# PD_Receiver_Circuit.net
KiCad netlist of a schematic drawn in Altium Designer
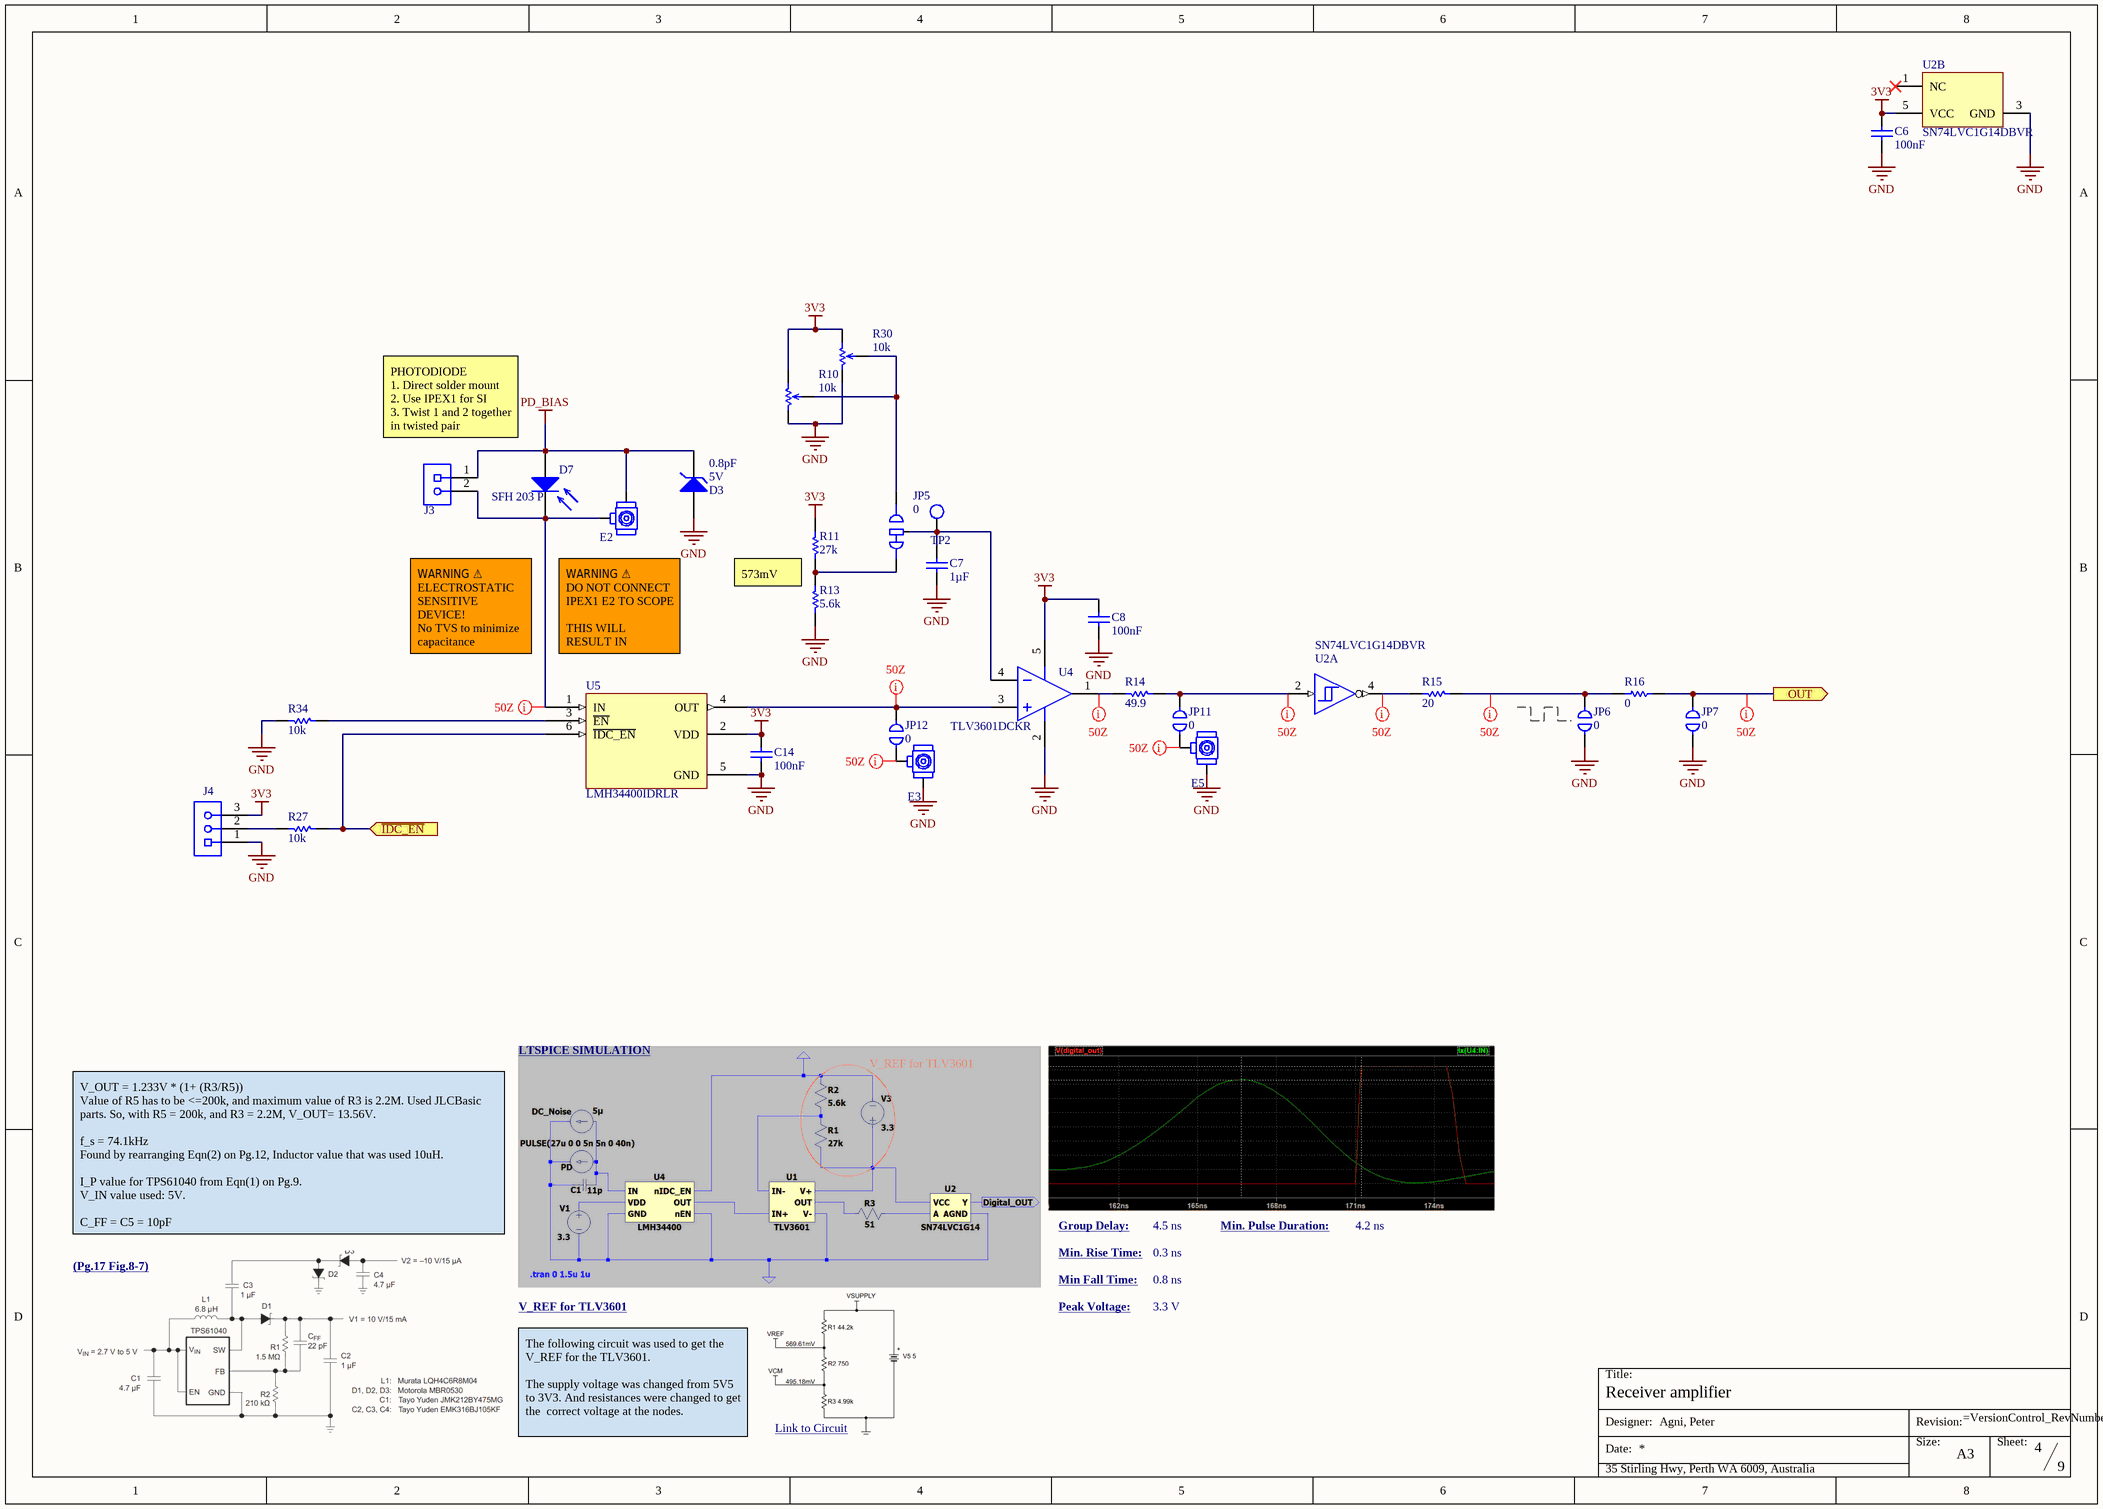
[diagram p0: PD_Receiver_Circuit.SchDoc]

(export (version "E")
  (design (tool "Eeschema 10.0.6"))
  (components
    (comp (ref "C6")
      (value "100nF")
      (footprint "CAPC1005X06N")
      (fields (field (name "TOLERANCE") "10%") (field (name "Comment") "CL05B104KB54PNC"))
      (libsource (lib "UWA Aerospace") (part "Capacitor - Non-polar"))
    )
    (comp (ref "C7")
      (value "1µF")
      (footprint "CAPC1005X06N")
      (fields (field (name "TOLERANCE") "10%") (field (name "Comment") "CL05A105KA5NQNC"))
      (libsource (lib "UWA Aerospace") (part "Capacitor - Non-polar"))
    )
    (comp (ref "C8")
      (value "100nF")
      (footprint "CAPC1005X06N")
      (fields (field (name "TOLERANCE") "10%") (field (name "Comment") "CL05B104KB54PNC"))
      (libsource (lib "UWA Aerospace") (part "Capacitor - Non-polar"))
    )
    (comp (ref "C14")
      (value "100nF")
      (footprint "CAPC1005X06N")
      (fields (field (name "TOLERANCE") "10%") (field (name "Comment") "CL05B104KB54PNC"))
      (libsource (lib "UWA Aerospace") (part "Capacitor - Non-polar"))
    )
    (comp (ref "D3")
      (value "5V")
      (footprint "DFN60P100X45-2L")
      (description "5A 55W 16V 9V Unidirectional 5V DFN1006-2L  ESD and Surge Protection (TVS/ESD) ROHS")
      (fields (field (name "CAPACITANCE") "0.8pF") (field (name "Comment") "H5VU10U"))
      (libsource (lib "UWA Aerospace") (part "Diode - Zener"))
    )
    (comp (ref "D7")
      (value "SFH 203 P")
      (footprint "SFH203P")
      (description "Photodiode PIN Chip 850nm 0.62A/W Sensitivity 2-Pin T-1 3/4")
      (fields (field (name "SOURCE") "Distributor"))
      (libsource (lib "UWA Aerospace") (part "Photodiode"))
    )
    (comp (ref "E2")
      (value "U.FL-R-SMT-1(01)")
      (footprint "HRS-U.FL-R-SMT-3_V 4_LAYER_KO")
      (description "Rf Connectors / Coaxial Connectors SMT Ml Rec Au 50 Ohm W/anti Sldr Wicking UFL")
      (fields (field (name "SOURCE") "UWAA_Stock"))
      (libsource (lib "") (part "U.FL Connector_1"))
    )
    (comp (ref "E3")
      (value "U.FL-R-SMT-1(01)")
      (footprint "HRS-U.FL-R-SMT-3_V 4_LAYER_KO")
      (description "Rf Connectors / Coaxial Connectors SMT Ml Rec Au 50 Ohm W/anti Sldr Wicking UFL")
      (fields (field (name "SOURCE") "UWAA_Stock"))
      (libsource (lib "UWA Aerospace") (part "U.FL Connector"))
    )
    (comp (ref "E5")
      (value "U.FL-R-SMT-1(01)")
      (footprint "HRS-U.FL-R-SMT-3_V 4_LAYER_KO")
      (description "Rf Connectors / Coaxial Connectors SMT Ml Rec Au 50 Ohm W/anti Sldr Wicking UFL")
      (fields (field (name "SOURCE") "UWAA_Stock"))
      (libsource (lib "UWA Aerospace") (part "U.FL Connector"))
    )
    (comp (ref "J3")
      (value "B2B-PH-K-S(LF)(SN)")
      (footprint "JST_B2B-PH-K-S(LF)(SN)")
      (libsource (lib "UWA Aerospace") (part "Connector - 1x2 Single Sided"))
    )
    (comp (ref "J4")
      (value "10129378-903001BLF")
      (footprint "10129378-903001BLF-Footprint-1")
      (description "Conn Unshrouded Header HDR 3 POS 2.54mm Solder ST Thru-Hole Poly Bag")
      (fields (field (name "SOURCE") "Aliexpress"))
      (libsource (lib "UWA Aerospace") (part "10129378-903001BLF"))
    )
    (comp (ref "JP5")
      (value "0")
      (footprint "RESC1005X04N TWO STATE")
      (description "JUMPER-0402 TWO STATE Fixed Resistor, Metal Glaze/thick Film, 0.1W, 0ohm, Surface Mount, 0402")
      (fields (field (name "TOLERANCE") "1%") (field (name "Comment") "JUMPER-0402 TWO STATE"))
      (libsource (lib "UWA Aerospace") (part "Jumper - Two state"))
    )
    (comp (ref "JP6")
      (value "0")
      (footprint "RESC1005X04N")
      (description "0402 pad placeholder for 0-ohm resistor jumper")
      (fields
        (field (name "TOLERANCE") "1%")
        (field (name "Comment") "JUMPER-0402")
        (field (name "SOURCE") "Distributor")
      )
      (libsource (lib "UWA Aerospace") (part "Jumper - Open"))
    )
    (comp (ref "JP7")
      (value "0")
      (footprint "RESC1005X04N")
      (description "0402 pad placeholder for 0-ohm resistor jumper")
      (fields
        (field (name "TOLERANCE") "1%")
        (field (name "Comment") "JUMPER-0402")
        (field (name "SOURCE") "Distributor")
      )
      (libsource (lib "UWA Aerospace") (part "Jumper - Open"))
    )
    (comp (ref "JP11")
      (value "0")
      (footprint "RESC1005X04N")
      (description "0402 pad placeholder for 0-ohm resistor jumper")
      (fields
        (field (name "TOLERANCE") "1%")
        (field (name "Comment") "JUMPER-0402")
        (field (name "SOURCE") "Distributor")
      )
      (libsource (lib "UWA Aerospace") (part "Jumper - Open"))
    )
    (comp (ref "JP12")
      (value "0")
      (footprint "RESC1005X04N")
      (description "0402 pad placeholder for 0-ohm resistor jumper")
      (fields
        (field (name "TOLERANCE") "1%")
        (field (name "Comment") "JUMPER-0402")
        (field (name "SOURCE") "Distributor")
      )
      (libsource (lib "UWA Aerospace") (part "Jumper - Open"))
    )
    (comp (ref "R10")
      (value "10k")
      (footprint "BOUR-TC33X-2_V")
      (description "Res Trimmer 10K Ohm 25% 1/10W 1(Elec)/1(Mech)Turn (3 X 3.8mm) Foot Print SMD Embossed T/R")
      (fields (field (name "TOLERANCE") "25%") (field (name "Comment") "TC33X-2-103E"))
      (libsource (lib "UWA Aerospace") (part "Resistor - Adjustable"))
    )
    (comp (ref "R11")
      (value "27k")
      (footprint "RESC1005X04N")
      (description "Res Thick Film 0402 27K Ohm 1% 0.063W(1/16W) ±100ppm/C Pad SMD T/R")
      (fields (field (name "TOLERANCE") "1%") (field (name "Comment") "0402WGF2702TCE"))
      (libsource (lib "UWA Aerospace") (part "Resistor"))
    )
    (comp (ref "R13")
      (value "5.6k")
      (footprint "RESC1005X04N")
      (description "62.5mW Thick Film Resistors 50V ±100ppm/℃ ±1% 5.6kΩ 0402 Chip Resistor - Surface Mount ROHS")
      (fields (field (name "TOLERANCE") "1%") (field (name "Comment") "0402WGF5601TCE"))
      (libsource (lib "UWA Aerospace") (part "Resistor"))
    )
    (comp (ref "R14")
      (value "49.9")
      (footprint "RESC1005X04N")
      (description "62.5mW Thick Film Resistors 50V ±100ppm/℃ ±1% 49.9Ω 0402 Chip Resistor - Surface Mount ROHS")
      (fields (field (name "TOLERANCE") "1%") (field (name "Comment") "0402WGF499JTCE"))
      (libsource (lib "UWA Aerospace") (part "Resistor"))
    )
    (comp (ref "R15")
      (value "20")
      (footprint "RESC1608X05N")
      (description "Res Thick Film 0603 20 Ohm 1% 0.1W(1/10W) ±200ppm/C Pad SMD T/R")
      (fields (field (name "TOLERANCE") "1%") (field (name "Comment") "0603WAF200JT5E"))
      (libsource (lib "UWA Aerospace") (part "Resistor"))
    )
    (comp (ref "R16")
      (value "0")
      (footprint "RESC1005X04N")
      (description "Metal Glaze/thick Film, 0.0625W, 0ohm, 0402")
      (fields (field (name "TOLERANCE") "1%") (field (name "Comment") "0402WGF0000TCE"))
      (libsource (lib "UWA Aerospace") (part "Resistor"))
    )
    (comp (ref "R27")
      (value "10k")
      (footprint "RESC1005X04N")
      (description "Res Thick Film 0402 10K Ohm 1% 1/16W ±100ppm/°C Molded SMD Paper T/R")
      (fields (field (name "TOLERANCE") "1%") (field (name "Comment") "CRCW0402-10K0FKED"))
      (libsource (lib "UWA Aerospace") (part "Resistor"))
    )
    (comp (ref "R30")
      (value "10k")
      (footprint "POT_RK0971-L-15KC_N-1")
      (description "Potentiometer, 0.05W, 10000ohm, 10V, 20% +/-Tol, 1 Turn(s)")
      (fields
        (field (name "TOLERANCE") "20%")
        (field (name "Comment") "RK0971114D0B")
        (field (name "SOURCE") "Aliexpress")
      )
      (libsource (lib "UWA Aerospace") (part "Resistor - Adjustable"))
    )
    (comp (ref "R34")
      (value "10k")
      (footprint "RESC1005X04N")
      (description "Res Thick Film 0402 10K Ohm 1% 1/16W ±100ppm/°C Molded SMD Paper T/R")
      (fields (field (name "TOLERANCE") "1%") (field (name "Comment") "CRCW0402-10K0FKED"))
      (libsource (lib "UWA Aerospace") (part "Resistor"))
    )
    (comp (ref "TP2")
      (value "Test Point 5001")
      (footprint "FP-5001-MFG")
      (fields (field (name "SOURCE") "UWAA_Stock"))
      (libsource (lib "UWA Aerospace") (part "Test Point"))
    )
    (comp (ref "U2")
      (value "SN74LVC1G14DBVR")
      (footprint "DBV0005A_N")
      (description "Single 1.65-V to 5.5-V inverter with Schmitt-Trigger inputs 5-SOT-23 -40 to 125")
      (fields (field (name "SOURCE") "Distributor"))
      (libsource (lib "UWA Aerospace") (part "TI-SN74XXX1XX4-XX-5-SCHMITT"))
    )
    (comp (ref "U4")
      (value "TLV3601DCKR")
      (footprint "DCK0005A_SC-70-5_TI_SOT65P210X110-5N")
      (description "2.5-ns high-speed rail-to-rail comparator with push-pull outputs 5-SC70 -40 to 125")
      (fields (field (name "SOURCE") "JLCPCB(Extended,Economic_PCBA)"))
      (libsource (lib "UWA Aerospace") (part "SOT-23 Opamp Standard"))
    )
    (comp (ref "U5")
      (value "LMH34400IDRLR")
      (footprint "SOTFL50P160X60-6N")
      (description "\"240-MHZ, Single-ended, Transimpe\" Transimpedance Amplifier IC SOT-563")
      (fields (field (name "SOURCE") "JLCPCB(Extended,Economic_PCBA)"))
      (libsource (lib "UWA Aerospace") (part "LMH34400IDRLR-Symbol-1"))
    )
  )
  (nets
    (net (code "1") (name "/OUT") (class "Default")
      (node (ref "JP7") (pin "2") (pinfunction "2_2") (pintype "passive"))
      (node (ref "R16") (pin "1") (pinfunction "1_1") (pintype "passive"))
    )
    (net (code "2") (name "/~{IDC_EN}") (class "Default")
      (node (ref "R27") (pin "1") (pinfunction "1_1") (pintype "passive"))
      (node (ref "U5") (pin "6") (pinfunction "~{IDC_EN}_6") (pintype "input"))
    )
    (net (code "3") (name "3V3") (class "Default")
      (node (ref "C14") (pin "2") (pinfunction "2_2") (pintype "passive"))
      (node (ref "C6") (pin "2") (pinfunction "2_2") (pintype "passive"))
      (node (ref "C8") (pin "2") (pinfunction "2_2") (pintype "passive"))
      (node (ref "J4") (pin "3") (pinfunction "3_3") (pintype "passive"))
      (node (ref "R10") (pin "3") (pinfunction "CW_3") (pintype "passive"))
      (node (ref "R11") (pin "2") (pinfunction "2_2") (pintype "passive"))
      (node (ref "R30") (pin "3") (pinfunction "CW_3") (pintype "passive"))
      (node (ref "U2") (pin "5") (pinfunction "VCC_5") (pintype "power_in"))
      (node (ref "U4") (pin "5") (pinfunction "V+_5") (pintype "passive"))
      (node (ref "U5") (pin "2") (pinfunction "VDD_2") (pintype "power_in"))
    )
    (net (code "4") (name "GND") (class "Default")
      (node (ref "C14") (pin "1") (pinfunction "1_1") (pintype "passive"))
      (node (ref "C6") (pin "1") (pinfunction "1_1") (pintype "passive"))
      (node (ref "C7") (pin "1") (pinfunction "1_1") (pintype "passive"))
      (node (ref "C8") (pin "1") (pinfunction "1_1") (pintype "passive"))
      (node (ref "D3") (pin "2") (pinfunction "A_2") (pintype "passive"))
      (node (ref "E3") (pin "2") (pinfunction "GND_2") (pintype "passive"))
      (node (ref "E5") (pin "2") (pinfunction "GND_2") (pintype "passive"))
      (node (ref "J4") (pin "1") (pinfunction "1_1") (pintype "passive"))
      (node (ref "JP6") (pin "1") (pinfunction "1_1") (pintype "passive"))
      (node (ref "JP7") (pin "1") (pinfunction "1_1") (pintype "passive"))
      (node (ref "R10") (pin "1") (pinfunction "CCW_1") (pintype "passive"))
      (node (ref "R13") (pin "1") (pinfunction "1_1") (pintype "passive"))
      (node (ref "R30") (pin "1") (pinfunction "CCW_1") (pintype "passive"))
      (node (ref "R34") (pin "2") (pinfunction "2_2") (pintype "passive"))
      (node (ref "U2") (pin "3") (pinfunction "GND_3") (pintype "power_in"))
      (node (ref "U4") (pin "2") (pinfunction "V-_2") (pintype "passive"))
      (node (ref "U5") (pin "5") (pinfunction "GND_5") (pintype "power_in"))
    )
    (net (code "5") (name "Net-(D7-K)") (class "Default")
      (node (ref "D7") (pin "1") (pinfunction "K_1") (pintype "passive"))
      (node (ref "E2") (pin "1") (pinfunction "SIG_1") (pintype "passive"))
      (node (ref "J3") (pin "2") (pinfunction "2_2") (pintype "passive"))
      (node (ref "U5") (pin "1") (pinfunction "IN_1") (pintype "input"))
    )
    (net (code "6") (name "Net-(E3-SIG)") (class "Default")
      (node (ref "E3") (pin "1") (pinfunction "SIG_1") (pintype "passive"))
      (node (ref "JP12") (pin "1") (pinfunction "1_1") (pintype "passive"))
    )
    (net (code "7") (name "Net-(E5-SIG)") (class "Default")
      (node (ref "E5") (pin "1") (pinfunction "SIG_1") (pintype "passive"))
      (node (ref "JP11") (pin "1") (pinfunction "1_1") (pintype "passive"))
    )
    (net (code "8") (name "Net-(J4-Pad2)") (class "Default")
      (node (ref "J4") (pin "2") (pinfunction "2_2") (pintype "passive"))
      (node (ref "R27") (pin "2") (pinfunction "2_2") (pintype "passive"))
    )
    (net (code "9") (name "Net-(JP5-COM)") (class "Default")
      (node (ref "C7") (pin "2") (pinfunction "2_2") (pintype "passive"))
      (node (ref "JP5") (pin "3") (pinfunction "COM_3") (pintype "passive"))
      (node (ref "TP2") (pin "1") (pinfunction "1_1") (pintype "passive"))
      (node (ref "U4") (pin "4") (pinfunction "IN-_4") (pintype "passive"))
    )
    (net (code "10") (name "Net-(JP5-Pad2)") (class "Default")
      (node (ref "JP5") (pin "2") (pinfunction "2_2") (pintype "passive"))
      (node (ref "R11") (pin "1") (pinfunction "1_1") (pintype "passive"))
      (node (ref "R13") (pin "2") (pinfunction "2_2") (pintype "passive"))
    )
    (net (code "11") (name "Net-(JP6-Pad2)") (class "Default")
      (node (ref "JP6") (pin "2") (pinfunction "2_2") (pintype "passive"))
      (node (ref "R15") (pin "2") (pinfunction "2_2") (pintype "passive"))
      (node (ref "R16") (pin "2") (pinfunction "2_2") (pintype "passive"))
    )
    (net (code "12") (name "Net-(R10-W)") (class "Default")
      (node (ref "JP5") (pin "1") (pinfunction "1_1") (pintype "passive"))
      (node (ref "R10") (pin "2") (pinfunction "W_2") (pintype "passive"))
      (node (ref "R30") (pin "2") (pinfunction "W_2") (pintype "passive"))
    )
    (net (code "13") (name "Net-(U2A-A)") (class "Default")
      (node (ref "JP11") (pin "2") (pinfunction "2_2") (pintype "passive"))
      (node (ref "R14") (pin "2") (pinfunction "2_2") (pintype "passive"))
      (node (ref "U2") (pin "2") (pinfunction "A_2") (pintype "input"))
    )
    (net (code "14") (name "Net-(U2A-Y)") (class "Default")
      (node (ref "R15") (pin "1") (pinfunction "1_1") (pintype "passive"))
      (node (ref "U2") (pin "4") (pinfunction "Y_4") (pintype "output"))
    )
    (net (code "15") (name "Net-(U4-IN+)") (class "Default")
      (node (ref "JP12") (pin "2") (pinfunction "2_2") (pintype "passive"))
      (node (ref "U4") (pin "3") (pinfunction "IN+_3") (pintype "passive"))
      (node (ref "U5") (pin "4") (pinfunction "OUT_4") (pintype "output"))
    )
    (net (code "16") (name "Net-(U4-OUT)") (class "Default")
      (node (ref "R14") (pin "1") (pinfunction "1_1") (pintype "passive"))
      (node (ref "U4") (pin "1") (pinfunction "OUT_1") (pintype "passive"))
    )
    (net (code "17") (name "Net-(U5-~{EN})") (class "Default")
      (node (ref "R34") (pin "1") (pinfunction "1_1") (pintype "passive"))
      (node (ref "U5") (pin "3") (pinfunction "~{EN}_3") (pintype "input"))
    )
    (net (code "18") (name "PD_BIAS") (class "Default")
      (node (ref "D3") (pin "1") (pinfunction "K_1") (pintype "passive"))
      (node (ref "D7") (pin "2") (pinfunction "A_2") (pintype "passive"))
      (node (ref "E2") (pin "2") (pinfunction "GND_2") (pintype "passive"))
      (node (ref "J3") (pin "1") (pinfunction "1_1") (pintype "passive"))
    )
    (net (code "19") (name "unconnected-(U2B-NC-Pad1)") (class "Default")
      (node (ref "U2") (pin "1") (pinfunction "NC_1") (pintype "passive+no_connect"))
    )
  )
)
